# Pasa_Banda_Superior.net
KiCad netlist of a schematic drawn in Altium Designer
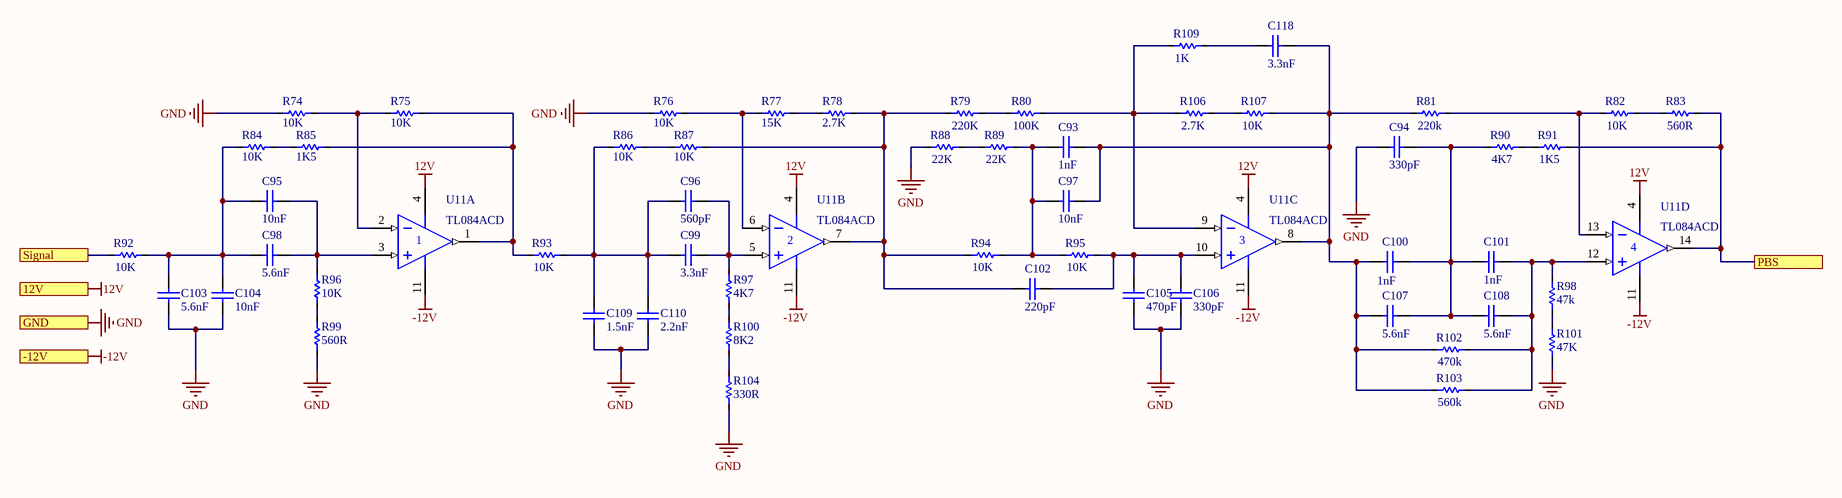
[diagram p0: Pasa Banda Superior.SchDoc]

(export (version "E")
  (design (tool "Eeschema 10.0.6"))
  (components
    (comp (ref "C93")
      (value "Cap Ceramico Disco")
      (footprint "CAP DISCO 200mil")
      (description "Capacitor Ceramico de Insercion")
      (fields (field (name "VALOR") "1nF"))
      (libsource (lib "RUF-Dispositivos-Grales") (part "Cap Ceramico Disco"))
    )
    (comp (ref "C94")
      (value "Cap Ceramico Disco")
      (footprint "cap 10")
      (description "Capacitor Ceramico de Insercion")
      (fields (field (name "VALOR") "330pF"))
      (libsource (lib "RUF-Dispositivos-Grales") (part "Cap Ceramico Disco"))
    )
    (comp (ref "C95")
      (value "Cap Ceramico Disco")
      (footprint "cap 10")
      (description "Capacitor Ceramico de Insercion")
      (fields (field (name "VALOR") "10nF"))
      (libsource (lib "RUF-Dispositivos-Grales") (part "Cap Ceramico Disco"))
    )
    (comp (ref "C96")
      (value "Cap Ceramico Disco")
      (footprint "CAP DISCO 200mil")
      (description "Capacitor Ceramico de Insercion")
      (fields (field (name "VALOR") "560pF"))
      (libsource (lib "RUF-Dispositivos-Grales") (part "Cap Ceramico Disco"))
    )
    (comp (ref "C97")
      (value "Cap Ceramico Disco")
      (footprint "CAP DISCO 200mil")
      (description "Capacitor Ceramico de Insercion")
      (fields (field (name "VALOR") "10nF"))
      (libsource (lib "RUF-Dispositivos-Grales") (part "Cap Ceramico Disco"))
    )
    (comp (ref "C98")
      (value "Cap Ceramico Disco")
      (footprint "CAP DISCO 200mil")
      (description "Capacitor Ceramico de Insercion")
      (fields (field (name "VALOR") "5.6nF"))
      (libsource (lib "RUF-Dispositivos-Grales") (part "Cap Ceramico Disco"))
    )
    (comp (ref "C99")
      (value "Cap Ceramico Disco")
      (footprint "CAP DISCO 200mil")
      (description "Capacitor Ceramico de Insercion")
      (fields (field (name "VALOR") "3.3nF"))
      (libsource (lib "RUF-Dispositivos-Grales") (part "Cap Ceramico Disco"))
    )
    (comp (ref "C100")
      (value "Cap Ceramico Disco")
      (footprint "CAP DISCO 200mil")
      (description "Capacitor Ceramico de Insercion")
      (fields (field (name "VALOR") "1nF"))
      (libsource (lib "RUF-Dispositivos-Grales") (part "Cap Ceramico Disco"))
    )
    (comp (ref "C101")
      (value "Cap Ceramico Disco")
      (footprint "CAP DISCO 200mil")
      (description "Capacitor Ceramico de Insercion")
      (fields (field (name "VALOR") "1nF"))
      (libsource (lib "RUF-Dispositivos-Grales") (part "Cap Ceramico Disco"))
    )
    (comp (ref "C102")
      (value "Cap Ceramico Disco")
      (footprint "CAP DISCO 200mil")
      (description "Capacitor Ceramico de Insercion")
      (fields (field (name "VALOR") "220pF"))
      (libsource (lib "RUF-Dispositivos-Grales") (part "Cap Ceramico Disco"))
    )
    (comp (ref "C103")
      (value "Cap Ceramico Disco")
      (footprint "CAP DISCO 200mil")
      (description "Capacitor Ceramico de Insercion")
      (fields (field (name "VALOR") "5.6nF"))
      (libsource (lib "RUF-Dispositivos-Grales") (part "Cap Ceramico Disco"))
    )
    (comp (ref "C104")
      (value "Cap Ceramico Disco")
      (footprint "cap 10")
      (description "Capacitor Ceramico de Insercion")
      (fields (field (name "VALOR") "10nF"))
      (libsource (lib "RUF-Dispositivos-Grales") (part "Cap Ceramico Disco"))
    )
    (comp (ref "C105")
      (value "Cap Ceramico Disco")
      (footprint "cap 10")
      (description "Capacitor Ceramico de Insercion")
      (fields (field (name "VALOR") "470pF"))
      (libsource (lib "RUF-Dispositivos-Grales") (part "Cap Ceramico Disco"))
    )
    (comp (ref "C106")
      (value "Cap Ceramico Disco")
      (footprint "CAP DISCO 150mil")
      (description "Capacitor Ceramico de Insercion")
      (fields (field (name "VALOR") "330pF"))
      (libsource (lib "RUF-Dispositivos-Grales") (part "Cap Ceramico Disco"))
    )
    (comp (ref "C107")
      (value "Cap Ceramico Disco")
      (footprint "CAP DISCO 200mil")
      (description "Capacitor Ceramico de Insercion")
      (fields (field (name "VALOR") "5.6nF"))
      (libsource (lib "RUF-Dispositivos-Grales") (part "Cap Ceramico Disco"))
    )
    (comp (ref "C108")
      (value "Cap Ceramico Disco")
      (footprint "CAP DISCO 200mil")
      (description "Capacitor Ceramico de Insercion")
      (fields (field (name "VALOR") "5.6nF"))
      (libsource (lib "RUF-Dispositivos-Grales") (part "Cap Ceramico Disco"))
    )
    (comp (ref "C109")
      (value "Cap Ceramico Disco")
      (footprint "cap 10")
      (description "Capacitor Ceramico de Insercion")
      (fields (field (name "VALOR") "1.5nF"))
      (libsource (lib "RUF-Dispositivos-Grales") (part "Cap Ceramico Disco"))
    )
    (comp (ref "C110")
      (value "Cap Ceramico Disco")
      (footprint "cap 10")
      (description "Capacitor Ceramico de Insercion")
      (fields (field (name "VALOR") "2.2nF"))
      (libsource (lib "RUF-Dispositivos-Grales") (part "Cap Ceramico Disco"))
    )
    (comp (ref "C118")
      (value "Cap Ceramico Disco")
      (footprint "CAP DISCO 200mil")
      (description "Capacitor Ceramico de Insercion")
      (fields (field (name "VALOR") "3.3nF"))
      (libsource (lib "RUF-Dispositivos-Grales") (part "Cap Ceramico Disco"))
    )
    (comp (ref "R74")
      (value "Res SMD")
      (footprint "1206 resistor")
      (description "Res Smd")
      (fields (field (name "VALOR") "10K"))
      (libsource (lib "RUF-Dispositivos-Grales") (part "Res SMD"))
    )
    (comp (ref "R75")
      (value "Res SMD")
      (footprint "1206 resistor")
      (description "Res Smd")
      (fields (field (name "VALOR") "10K"))
      (libsource (lib "RUF-Dispositivos-Grales") (part "Res SMD"))
    )
    (comp (ref "R76")
      (value "Res SMD")
      (footprint "1206 resistor")
      (description "Res Smd")
      (fields (field (name "VALOR") "10K"))
      (libsource (lib "RUF-Dispositivos-Grales") (part "Res SMD"))
    )
    (comp (ref "R77")
      (value "Res SMD")
      (footprint "1206 resistor")
      (description "Res Smd")
      (fields (field (name "VALOR") "15K"))
      (libsource (lib "RUF-Dispositivos-Grales") (part "Res SMD"))
    )
    (comp (ref "R78")
      (value "Res SMD")
      (footprint "1206 resistor")
      (description "Res Smd")
      (fields (field (name "VALOR") "2.7K"))
      (libsource (lib "RUF-Dispositivos-Grales") (part "Res SMD"))
    )
    (comp (ref "R79")
      (value "Res SMD")
      (footprint "RES AXIAL 400mil")
      (description "Res Smd")
      (fields (field (name "VALOR") "220K"))
      (libsource (lib "RUF-Dispositivos-Grales") (part "Res SMD"))
    )
    (comp (ref "R80")
      (value "Res SMD")
      (footprint "RES AXIAL 400mil")
      (description "Res Smd")
      (fields (field (name "VALOR") "100K"))
      (libsource (lib "RUF-Dispositivos-Grales") (part "Res SMD"))
    )
    (comp (ref "R81")
      (value "Res SMD")
      (footprint "RES AXIAL 400mil")
      (description "Res Smd")
      (fields (field (name "VALOR") "220k"))
      (libsource (lib "RUF-Dispositivos-Grales") (part "Res SMD"))
    )
    (comp (ref "R82")
      (value "Res SMD")
      (footprint "1206 resistor")
      (description "Res Smd")
      (fields (field (name "VALOR") "10K"))
      (libsource (lib "RUF-Dispositivos-Grales") (part "Res SMD"))
    )
    (comp (ref "R83")
      (value "Res SMD")
      (footprint "1206 resistor")
      (description "Res Smd")
      (fields (field (name "VALOR") "560R"))
      (libsource (lib "RUF-Dispositivos-Grales") (part "Res SMD"))
    )
    (comp (ref "R84")
      (value "Res SMD")
      (footprint "1206 resistor")
      (description "Res Smd")
      (fields (field (name "VALOR") "10K"))
      (libsource (lib "RUF-Dispositivos-Grales") (part "Res SMD"))
    )
    (comp (ref "R85")
      (value "Res SMD")
      (footprint "1206 resistor")
      (description "Res Smd")
      (fields (field (name "VALOR") "1K5"))
      (libsource (lib "RUF-Dispositivos-Grales") (part "Res SMD"))
    )
    (comp (ref "R86")
      (value "Res SMD")
      (footprint "1206 resistor")
      (description "Res Smd")
      (fields (field (name "VALOR") "10K"))
      (libsource (lib "RUF-Dispositivos-Grales") (part "Res SMD"))
    )
    (comp (ref "R87")
      (value "Res SMD")
      (footprint "1206 resistor")
      (description "Res Smd")
      (fields (field (name "VALOR") "10K"))
      (libsource (lib "RUF-Dispositivos-Grales") (part "Res SMD"))
    )
    (comp (ref "R88")
      (value "Res SMD")
      (footprint "1206 resistor")
      (description "Res Smd")
      (fields (field (name "VALOR") "22K"))
      (libsource (lib "RUF-Dispositivos-Grales") (part "Res SMD"))
    )
    (comp (ref "R89")
      (value "Res SMD")
      (footprint "1206 resistor")
      (description "Res Smd")
      (fields (field (name "VALOR") "22K"))
      (libsource (lib "RUF-Dispositivos-Grales") (part "Res SMD"))
    )
    (comp (ref "R90")
      (value "Res SMD")
      (footprint "1206 resistor")
      (description "Res Smd")
      (fields (field (name "VALOR") "4K7"))
      (libsource (lib "RUF-Dispositivos-Grales") (part "Res SMD"))
    )
    (comp (ref "R91")
      (value "Res SMD")
      (footprint "1206 resistor")
      (description "Res Smd")
      (fields (field (name "VALOR") "1K5"))
      (libsource (lib "RUF-Dispositivos-Grales") (part "Res SMD"))
    )
    (comp (ref "R92")
      (value "Res SMD")
      (footprint "1206 resistor")
      (description "Res Smd")
      (fields (field (name "VALOR") "10K"))
      (libsource (lib "RUF-Dispositivos-Grales") (part "Res SMD"))
    )
    (comp (ref "R93")
      (value "Res SMD")
      (footprint "1206 resistor")
      (description "Res Smd")
      (fields (field (name "VALOR") "10K"))
      (libsource (lib "RUF-Dispositivos-Grales") (part "Res SMD"))
    )
    (comp (ref "R94")
      (value "Res SMD")
      (footprint "1206 resistor")
      (description "Res Smd")
      (fields (field (name "VALOR") "10K"))
      (libsource (lib "RUF-Dispositivos-Grales") (part "Res SMD"))
    )
    (comp (ref "R95")
      (value "Res SMD")
      (footprint "1206 resistor")
      (description "Res Smd")
      (fields (field (name "VALOR") "10K"))
      (libsource (lib "RUF-Dispositivos-Grales") (part "Res SMD"))
    )
    (comp (ref "R96")
      (value "Res SMD")
      (footprint "1206 resistor")
      (description "Res Smd")
      (fields (field (name "VALOR") "10K"))
      (libsource (lib "RUF-Dispositivos-Grales") (part "Res SMD"))
    )
    (comp (ref "R97")
      (value "Res SMD")
      (footprint "1206 resistor")
      (description "Res Smd")
      (fields (field (name "VALOR") "4K7"))
      (libsource (lib "RUF-Dispositivos-Grales") (part "Res SMD"))
    )
    (comp (ref "R98")
      (value "Res SMD")
      (footprint "RES AXIAL 400mil")
      (description "Res Smd")
      (fields (field (name "VALOR") "47k"))
      (libsource (lib "RUF-Dispositivos-Grales") (part "Res SMD"))
    )
    (comp (ref "R99")
      (value "Res SMD")
      (footprint "1206 resistor")
      (description "Res Smd")
      (fields (field (name "VALOR") "560R"))
      (libsource (lib "RUF-Dispositivos-Grales") (part "Res SMD"))
    )
    (comp (ref "R100")
      (value "Res SMD")
      (footprint "1206 resistor")
      (description "Res Smd")
      (fields (field (name "VALOR") "8K2"))
      (libsource (lib "RUF-Dispositivos-Grales") (part "Res SMD"))
    )
    (comp (ref "R101")
      (value "Res SMD")
      (footprint "RES AXIAL 400mil")
      (description "Res Smd")
      (fields (field (name "VALOR") "47K"))
      (libsource (lib "RUF-Dispositivos-Grales") (part "Res SMD"))
    )
    (comp (ref "R102")
      (value "Res SMD")
      (footprint "RES AXIAL 400mil")
      (description "Res Smd")
      (fields (field (name "VALOR") "470k"))
      (libsource (lib "RUF-Dispositivos-Grales") (part "Res SMD"))
    )
    (comp (ref "R103")
      (value "Res SMD")
      (footprint "RES AXIAL 400mil")
      (description "Res Smd")
      (fields (field (name "VALOR") "560k"))
      (libsource (lib "RUF-Dispositivos-Grales") (part "Res SMD"))
    )
    (comp (ref "R104")
      (value "Res SMD")
      (footprint "1206 resistor")
      (description "Res Smd")
      (fields (field (name "VALOR") "330R"))
      (libsource (lib "RUF-Dispositivos-Grales") (part "Res SMD"))
    )
    (comp (ref "R106")
      (value "Res SMD")
      (footprint "1206 resistor")
      (description "Res Smd")
      (fields (field (name "VALOR") "2.7K"))
      (libsource (lib "Userlib") (part "Res SMD"))
    )
    (comp (ref "R107")
      (value "Res SMD")
      (footprint "1206 resistor")
      (description "Res Smd")
      (fields (field (name "VALOR") "10K"))
      (libsource (lib "RUF-Dispositivos-Grales") (part "Res SMD"))
    )
    (comp (ref "R109")
      (value "Res SMD")
      (footprint "1206 resistor")
      (description "Res Smd")
      (fields (field (name "VALOR") "1K"))
      (libsource (lib "RUF-Dispositivos-Grales") (part "Res SMD"))
    )
    (comp (ref "U11")
      (value "TL084ACD")
      (footprint "751A-02_N")
      (description "JFET-Input Operational Amplifier")
      (fields (field (name "PUBLISHER") "Altium Limited"))
      (libsource (lib "Motorola Amplifier Operational Amplifier") (part "TL084ACD"))
    )
  )
  (nets
    (net (code "1") (name "-12V") (class "Default")
      (node (ref "U11") (pin "11") (pinfunction "V-_11") (pintype "power_in"))
    )
    (net (code "2") (name "/PBS") (class "Default")
      (node (ref "R83") (pin "2") (pinfunction "2_2") (pintype "passive"))
      (node (ref "R91") (pin "2") (pinfunction "2_2") (pintype "passive"))
      (node (ref "U11") (pin "14") (pinfunction "OUT_14") (pintype "output"))
    )
    (net (code "3") (name "/Signal") (class "Default")
      (node (ref "R92") (pin "1") (pinfunction "1_1") (pintype "passive"))
    )
    (net (code "4") (name "12V") (class "Default")
      (node (ref "U11") (pin "4") (pinfunction "V+_4") (pintype "power_in"))
    )
    (net (code "5") (name "GND") (class "Default")
      (node (ref "C103") (pin "1") (pinfunction "1_1") (pintype "passive"))
      (node (ref "C104") (pin "1") (pinfunction "1_1") (pintype "passive"))
      (node (ref "C105") (pin "2") (pinfunction "2_2") (pintype "passive"))
      (node (ref "C106") (pin "2") (pinfunction "2_2") (pintype "passive"))
      (node (ref "C109") (pin "1") (pinfunction "1_1") (pintype "passive"))
      (node (ref "C110") (pin "1") (pinfunction "1_1") (pintype "passive"))
      (node (ref "C94") (pin "2") (pinfunction "2_2") (pintype "passive"))
      (node (ref "R101") (pin "1") (pinfunction "1_1") (pintype "passive"))
      (node (ref "R104") (pin "1") (pinfunction "1_1") (pintype "passive"))
      (node (ref "R74") (pin "2") (pinfunction "2_2") (pintype "passive"))
      (node (ref "R76") (pin "2") (pinfunction "2_2") (pintype "passive"))
      (node (ref "R88") (pin "1") (pinfunction "1_1") (pintype "passive"))
      (node (ref "R99") (pin "1") (pinfunction "1_1") (pintype "passive"))
    )
    (net (code "6") (name "Net-(C93-Pad2)") (class "Default")
      (node (ref "C93") (pin "2") (pinfunction "2_2") (pintype "passive"))
      (node (ref "C97") (pin "2") (pinfunction "2_2") (pintype "passive"))
      (node (ref "R89") (pin "2") (pinfunction "2_2") (pintype "passive"))
      (node (ref "R94") (pin "2") (pinfunction "2_2") (pintype "passive"))
      (node (ref "R95") (pin "1") (pinfunction "1_1") (pintype "passive"))
    )
    (net (code "7") (name "Net-(C100-Pad1)") (class "Default")
      (node (ref "C100") (pin "1") (pinfunction "1_1") (pintype "passive"))
      (node (ref "C101") (pin "2") (pinfunction "2_2") (pintype "passive"))
      (node (ref "C107") (pin "1") (pinfunction "1_1") (pintype "passive"))
      (node (ref "C108") (pin "2") (pinfunction "2_2") (pintype "passive"))
      (node (ref "C94") (pin "1") (pinfunction "1_1") (pintype "passive"))
      (node (ref "R90") (pin "1") (pinfunction "1_1") (pintype "passive"))
    )
    (net (code "8") (name "Net-(C103-Pad2)") (class "Default")
      (node (ref "C103") (pin "2") (pinfunction "2_2") (pintype "passive"))
      (node (ref "C104") (pin "2") (pinfunction "2_2") (pintype "passive"))
      (node (ref "C95") (pin "2") (pinfunction "2_2") (pintype "passive"))
      (node (ref "C98") (pin "2") (pinfunction "2_2") (pintype "passive"))
      (node (ref "R84") (pin "2") (pinfunction "2_2") (pintype "passive"))
      (node (ref "R92") (pin "2") (pinfunction "2_2") (pintype "passive"))
    )
    (net (code "9") (name "Net-(C109-Pad2)") (class "Default")
      (node (ref "C109") (pin "2") (pinfunction "2_2") (pintype "passive"))
      (node (ref "C110") (pin "2") (pinfunction "2_2") (pintype "passive"))
      (node (ref "C96") (pin "2") (pinfunction "2_2") (pintype "passive"))
      (node (ref "C99") (pin "2") (pinfunction "2_2") (pintype "passive"))
      (node (ref "R86") (pin "2") (pinfunction "2_2") (pintype "passive"))
      (node (ref "R93") (pin "2") (pinfunction "2_2") (pintype "passive"))
    )
    (net (code "10") (name "Net-(C118-Pad2)") (class "Default")
      (node (ref "C118") (pin "2") (pinfunction "2_2") (pintype "passive"))
      (node (ref "R109") (pin "2") (pinfunction "2_2") (pintype "passive"))
    )
    (net (code "11") (name "Net-(R77-Pad1)") (class "Default")
      (node (ref "R77") (pin "1") (pinfunction "1_1") (pintype "passive"))
      (node (ref "R78") (pin "2") (pinfunction "2_2") (pintype "passive"))
    )
    (net (code "12") (name "Net-(R79-Pad2)") (class "Default")
      (node (ref "R79") (pin "2") (pinfunction "2_2") (pintype "passive"))
      (node (ref "R80") (pin "1") (pinfunction "1_1") (pintype "passive"))
    )
    (net (code "13") (name "Net-(R82-Pad2)") (class "Default")
      (node (ref "R82") (pin "2") (pinfunction "2_2") (pintype "passive"))
      (node (ref "R83") (pin "1") (pinfunction "1_1") (pintype "passive"))
    )
    (net (code "14") (name "Net-(R84-Pad1)") (class "Default")
      (node (ref "R84") (pin "1") (pinfunction "1_1") (pintype "passive"))
      (node (ref "R85") (pin "2") (pinfunction "2_2") (pintype "passive"))
    )
    (net (code "15") (name "Net-(R86-Pad1)") (class "Default")
      (node (ref "R86") (pin "1") (pinfunction "1_1") (pintype "passive"))
      (node (ref "R87") (pin "2") (pinfunction "2_2") (pintype "passive"))
    )
    (net (code "16") (name "Net-(R88-Pad2)") (class "Default")
      (node (ref "R88") (pin "2") (pinfunction "2_2") (pintype "passive"))
      (node (ref "R89") (pin "1") (pinfunction "1_1") (pintype "passive"))
    )
    (net (code "17") (name "Net-(R90-Pad2)") (class "Default")
      (node (ref "R90") (pin "2") (pinfunction "2_2") (pintype "passive"))
      (node (ref "R91") (pin "1") (pinfunction "1_1") (pintype "passive"))
    )
    (net (code "18") (name "Net-(R96-Pad1)") (class "Default")
      (node (ref "R96") (pin "1") (pinfunction "1_1") (pintype "passive"))
      (node (ref "R99") (pin "2") (pinfunction "2_2") (pintype "passive"))
    )
    (net (code "19") (name "Net-(R100-Pad1)") (class "Default")
      (node (ref "R100") (pin "1") (pinfunction "1_1") (pintype "passive"))
      (node (ref "R104") (pin "2") (pinfunction "2_2") (pintype "passive"))
    )
    (net (code "20") (name "Net-(R100-Pad2)") (class "Default")
      (node (ref "R100") (pin "2") (pinfunction "2_2") (pintype "passive"))
      (node (ref "R97") (pin "1") (pinfunction "1_1") (pintype "passive"))
    )
    (net (code "21") (name "Net-(R101-Pad2)") (class "Default")
      (node (ref "R101") (pin "2") (pinfunction "2_2") (pintype "passive"))
      (node (ref "R98") (pin "1") (pinfunction "1_1") (pintype "passive"))
    )
    (net (code "22") (name "Net-(R106-Pad1)") (class "Default")
      (node (ref "R106") (pin "1") (pinfunction "1_1") (pintype "passive"))
      (node (ref "R107") (pin "2") (pinfunction "2_2") (pintype "passive"))
    )
    (net (code "23") (name "Net-(U11A-IN+)") (class "Default")
      (node (ref "C95") (pin "1") (pinfunction "1_1") (pintype "passive"))
      (node (ref "C98") (pin "1") (pinfunction "1_1") (pintype "passive"))
      (node (ref "R96") (pin "2") (pinfunction "2_2") (pintype "passive"))
      (node (ref "U11") (pin "3") (pinfunction "IN+_3") (pintype "input"))
    )
    (net (code "24") (name "Net-(U11A-IN-)") (class "Default")
      (node (ref "R74") (pin "1") (pinfunction "1_1") (pintype "passive"))
      (node (ref "R75") (pin "2") (pinfunction "2_2") (pintype "passive"))
      (node (ref "U11") (pin "2") (pinfunction "IN-_2") (pintype "input"))
    )
    (net (code "25") (name "Net-(U11A-OUT)") (class "Default")
      (node (ref "R75") (pin "1") (pinfunction "1_1") (pintype "passive"))
      (node (ref "R85") (pin "1") (pinfunction "1_1") (pintype "passive"))
      (node (ref "R93") (pin "1") (pinfunction "1_1") (pintype "passive"))
      (node (ref "U11") (pin "1") (pinfunction "OUT_1") (pintype "output"))
    )
    (net (code "26") (name "Net-(U11B-IN+)") (class "Default")
      (node (ref "C96") (pin "1") (pinfunction "1_1") (pintype "passive"))
      (node (ref "C99") (pin "1") (pinfunction "1_1") (pintype "passive"))
      (node (ref "R97") (pin "2") (pinfunction "2_2") (pintype "passive"))
      (node (ref "U11") (pin "5") (pinfunction "IN+_5") (pintype "input"))
    )
    (net (code "27") (name "Net-(U11B-IN-)") (class "Default")
      (node (ref "R76") (pin "1") (pinfunction "1_1") (pintype "passive"))
      (node (ref "R77") (pin "2") (pinfunction "2_2") (pintype "passive"))
      (node (ref "U11") (pin "6") (pinfunction "IN-_6") (pintype "input"))
    )
    (net (code "28") (name "Net-(U11B-OUT)") (class "Default")
      (node (ref "C102") (pin "2") (pinfunction "2_2") (pintype "passive"))
      (node (ref "R78") (pin "1") (pinfunction "1_1") (pintype "passive"))
      (node (ref "R79") (pin "1") (pinfunction "1_1") (pintype "passive"))
      (node (ref "R87") (pin "1") (pinfunction "1_1") (pintype "passive"))
      (node (ref "R94") (pin "1") (pinfunction "1_1") (pintype "passive"))
      (node (ref "U11") (pin "7") (pinfunction "OUT_7") (pintype "output"))
    )
    (net (code "29") (name "Net-(U11C-IN+)") (class "Default")
      (node (ref "C102") (pin "1") (pinfunction "1_1") (pintype "passive"))
      (node (ref "C105") (pin "1") (pinfunction "1_1") (pintype "passive"))
      (node (ref "C106") (pin "1") (pinfunction "1_1") (pintype "passive"))
      (node (ref "R95") (pin "2") (pinfunction "2_2") (pintype "passive"))
      (node (ref "U11") (pin "10") (pinfunction "IN+_10") (pintype "input"))
    )
    (net (code "30") (name "Net-(U11C-IN-)") (class "Default")
      (node (ref "R106") (pin "2") (pinfunction "2_2") (pintype "passive"))
      (node (ref "R109") (pin "1") (pinfunction "1_1") (pintype "passive"))
      (node (ref "R80") (pin "2") (pinfunction "2_2") (pintype "passive"))
      (node (ref "U11") (pin "9") (pinfunction "IN-_9") (pintype "input"))
    )
    (net (code "31") (name "Net-(U11C-OUT)") (class "Default")
      (node (ref "C100") (pin "2") (pinfunction "2_2") (pintype "passive"))
      (node (ref "C107") (pin "2") (pinfunction "2_2") (pintype "passive"))
      (node (ref "C118") (pin "1") (pinfunction "1_1") (pintype "passive"))
      (node (ref "C93") (pin "1") (pinfunction "1_1") (pintype "passive"))
      (node (ref "C97") (pin "1") (pinfunction "1_1") (pintype "passive"))
      (node (ref "R102") (pin "1") (pinfunction "1_1") (pintype "passive"))
      (node (ref "R103") (pin "1") (pinfunction "1_1") (pintype "passive"))
      (node (ref "R107") (pin "1") (pinfunction "1_1") (pintype "passive"))
      (node (ref "R81") (pin "1") (pinfunction "1_1") (pintype "passive"))
      (node (ref "U11") (pin "8") (pinfunction "OUT_8") (pintype "output"))
    )
    (net (code "32") (name "Net-(U11D-IN+)") (class "Default")
      (node (ref "C101") (pin "1") (pinfunction "1_1") (pintype "passive"))
      (node (ref "C108") (pin "1") (pinfunction "1_1") (pintype "passive"))
      (node (ref "R102") (pin "2") (pinfunction "2_2") (pintype "passive"))
      (node (ref "R103") (pin "2") (pinfunction "2_2") (pintype "passive"))
      (node (ref "R98") (pin "2") (pinfunction "2_2") (pintype "passive"))
      (node (ref "U11") (pin "12") (pinfunction "IN+_12") (pintype "input"))
    )
    (net (code "33") (name "Net-(U11D-IN-)") (class "Default")
      (node (ref "R81") (pin "2") (pinfunction "2_2") (pintype "passive"))
      (node (ref "R82") (pin "1") (pinfunction "1_1") (pintype "passive"))
      (node (ref "U11") (pin "13") (pinfunction "IN-_13") (pintype "input"))
    )
  )
)
